# pcb-bldc-servo-3.net
KiCad netlist of a schematic drawn in EAGLE
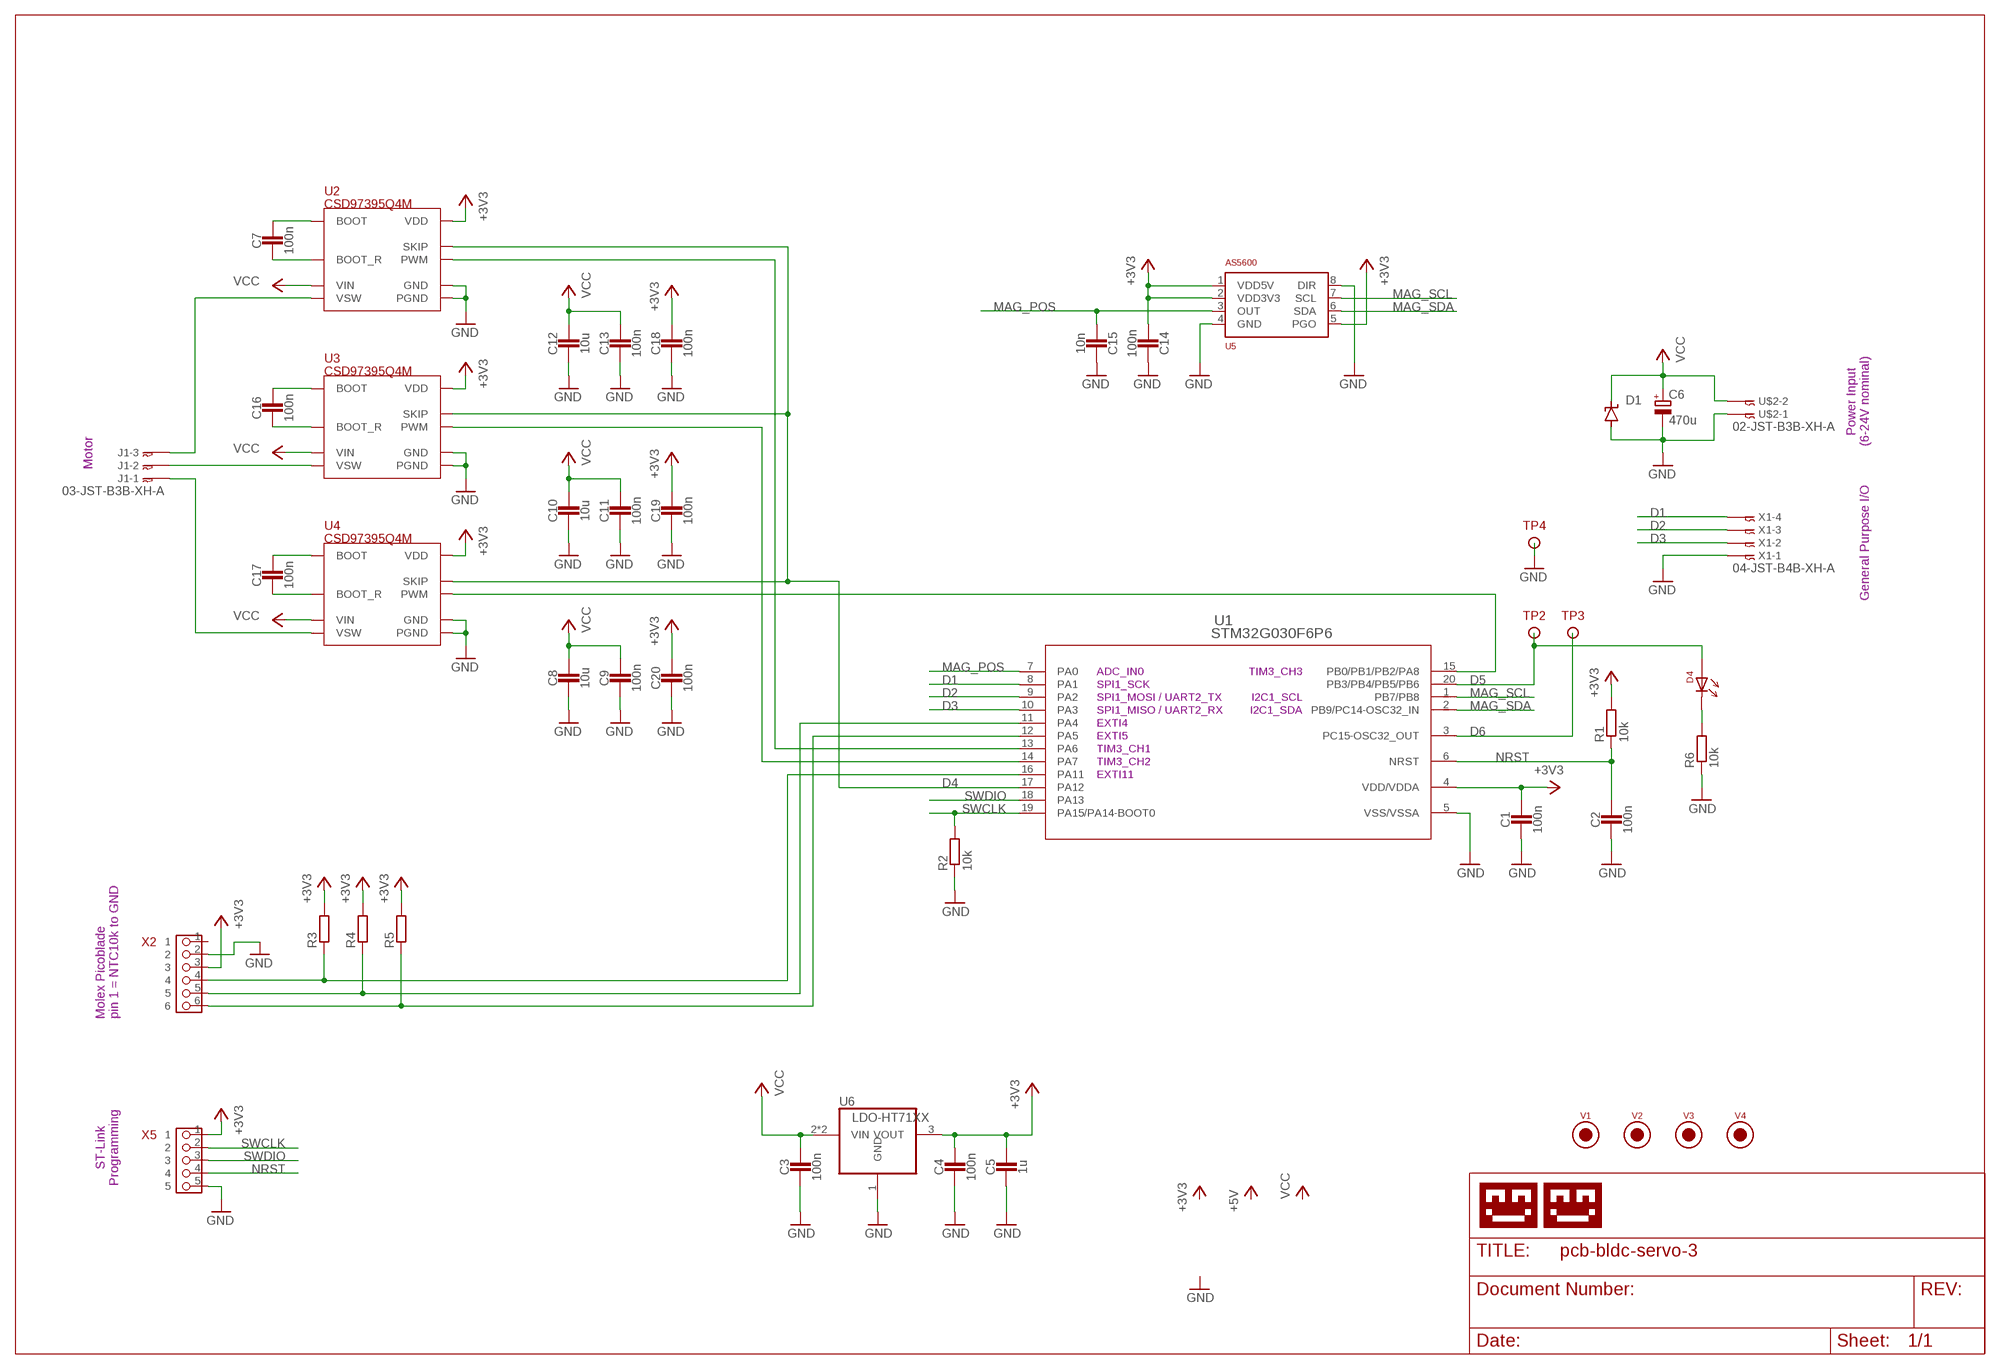
[diagram p0: schematic, sheet 1]

(export (version "E")
  (design (tool "Eeschema 10.0.6"))
  (components
    (comp (ref "C1")
      (value "100n")
      (footprint "eagle-import:0603_CAP")
      (libsource (lib "eagle-import") (part "CAPACITOR0603_CAP"))
    )
    (comp (ref "C2")
      (value "100n")
      (footprint "eagle-import:0603_CAP")
      (libsource (lib "eagle-import") (part "CAPACITOR0603_CAP"))
    )
    (comp (ref "C3")
      (value "100n")
      (footprint "eagle-import:0603_CAP")
      (libsource (lib "eagle-import") (part "CAPACITOR0603_CAP"))
    )
    (comp (ref "C4")
      (value "100n")
      (footprint "eagle-import:0603_CAP")
      (libsource (lib "eagle-import") (part "CAPACITOR0603_CAP"))
    )
    (comp (ref "C5")
      (value "1u")
      (footprint "eagle-import:0603_CAP")
      (libsource (lib "eagle-import") (part "CAPACITOR0603_CAP"))
    )
    (comp (ref "C6")
      (value "470u")
      (footprint "eagle-import:153CLV-1010")
      (libsource (lib "eagle-import") (part "CPOL-EU153CLV-1010"))
    )
    (comp (ref "C7")
      (value "100n")
      (footprint "eagle-import:0603_CAP")
      (libsource (lib "eagle-import") (part "CAPACITOR0603_CAP"))
    )
    (comp (ref "C8")
      (value "10u")
      (footprint "eagle-import:1206_CAP")
      (libsource (lib "eagle-import") (part "CAPACITOR1206_CAP"))
    )
    (comp (ref "C9")
      (value "100n")
      (footprint "eagle-import:0603_CAP")
      (libsource (lib "eagle-import") (part "CAPACITOR0603_CAP"))
    )
    (comp (ref "C10")
      (value "10u")
      (footprint "eagle-import:1206_CAP")
      (libsource (lib "eagle-import") (part "CAPACITOR1206_CAP"))
    )
    (comp (ref "C11")
      (value "100n")
      (footprint "eagle-import:0603_CAP")
      (libsource (lib "eagle-import") (part "CAPACITOR0603_CAP"))
    )
    (comp (ref "C12")
      (value "10u")
      (footprint "eagle-import:1206_CAP")
      (libsource (lib "eagle-import") (part "CAPACITOR1206_CAP"))
    )
    (comp (ref "C13")
      (value "100n")
      (footprint "eagle-import:0603_CAP")
      (libsource (lib "eagle-import") (part "CAPACITOR0603_CAP"))
    )
    (comp (ref "C14")
      (value "100n")
      (footprint "eagle-import:0603_CAP")
      (libsource (lib "eagle-import") (part "CAPACITOR0603_CAP"))
    )
    (comp (ref "C15")
      (value "10n")
      (footprint "eagle-import:0603_CAP")
      (libsource (lib "eagle-import") (part "CAPACITOR0603_CAP"))
    )
    (comp (ref "C16")
      (value "100n")
      (footprint "eagle-import:0603_CAP")
      (libsource (lib "eagle-import") (part "CAPACITOR0603_CAP"))
    )
    (comp (ref "C17")
      (value "100n")
      (footprint "eagle-import:0603_CAP")
      (libsource (lib "eagle-import") (part "CAPACITOR0603_CAP"))
    )
    (comp (ref "C18")
      (value "100n")
      (footprint "eagle-import:0603_CAP")
      (libsource (lib "eagle-import") (part "CAPACITOR0603_CAP"))
    )
    (comp (ref "C19")
      (value "100n")
      (footprint "eagle-import:0603_CAP")
      (libsource (lib "eagle-import") (part "CAPACITOR0603_CAP"))
    )
    (comp (ref "C20")
      (value "100n")
      (footprint "eagle-import:0603_CAP")
      (libsource (lib "eagle-import") (part "CAPACITOR0603_CAP"))
    )
    (comp (ref "D1")
      (value "SUPPRESSOR-SMBJ")
      (footprint "eagle-import:SMBJ")
      (libsource (lib "eagle-import") (part "SUPPRESSOR-SMBJ"))
    )
    (comp (ref "D4")
      (value "LED-0805")
      (footprint "eagle-import:0805-DOT")
      (libsource (lib "eagle-import") (part "LED-0805"))
    )
    (comp (ref "J1")
      (value "03-JST-B3B-XH-A")
      (footprint "eagle-import:B3B-XH")
      (libsource (lib "eagle-import") (part "03-JST-B3B-XH-A"))
    )
    (comp (ref "R1")
      (value "10k")
      (footprint "eagle-import:0603-RES")
      (libsource (lib "eagle-import") (part "RESISTOR0603_RES"))
    )
    (comp (ref "R2")
      (value "10k")
      (footprint "eagle-import:0603-RES")
      (libsource (lib "eagle-import") (part "RESISTOR0603_RES"))
    )
    (comp (ref "R3")
      (value "RESISTOR0603_RES")
      (footprint "eagle-import:0603-RES")
      (libsource (lib "eagle-import") (part "RESISTOR0603_RES"))
    )
    (comp (ref "R4")
      (value "RESISTOR0603_RES")
      (footprint "eagle-import:0603-RES")
      (libsource (lib "eagle-import") (part "RESISTOR0603_RES"))
    )
    (comp (ref "R5")
      (value "RESISTOR0603_RES")
      (footprint "eagle-import:0603-RES")
      (libsource (lib "eagle-import") (part "RESISTOR0603_RES"))
    )
    (comp (ref "R6")
      (value "10k")
      (footprint "eagle-import:0603-RES")
      (libsource (lib "eagle-import") (part "RESISTOR0603_RES"))
    )
    (comp (ref "TP2")
      (value "TESTPIN1MM")
      (footprint "eagle-import:PIN-SMD-1X1-TEST_1M0")
      (libsource (lib "eagle-import") (part "TESTPIN1MM"))
    )
    (comp (ref "TP3")
      (value "TESTPIN1MM")
      (footprint "eagle-import:PIN-SMD-1X1-TEST_1M0")
      (libsource (lib "eagle-import") (part "TESTPIN1MM"))
    )
    (comp (ref "TP4")
      (value "TESTPIN1MM")
      (footprint "eagle-import:PIN-SMD-1X1-TEST_1M0")
      (libsource (lib "eagle-import") (part "TESTPIN1MM"))
    )
    (comp (ref "U$1")
      (value "LOGO-TOBENG-1MM-FINISH")
      (footprint "eagle-import:TOBENG-1MM-FINISH")
      (libsource (lib "eagle-import") (part "LOGO-TOBENG-1MM-FINISH"))
    )
    (comp (ref "U$2")
      (value "02-JST-B3B-XH-A")
      (footprint "eagle-import:B2B-XH")
      (libsource (lib "eagle-import") (part "02-JST-B3B-XH-A"))
    )
    (comp (ref "U$3")
      (value "LOGO-TOBENG-4MM-FINISH")
      (footprint "eagle-import:TOBENG-4MM-FINISH")
      (libsource (lib "eagle-import") (part "LOGO-TOBENG-4MM-FINISH"))
    )
    (comp (ref "U1")
      (value "STM32G030F6P6")
      (footprint "eagle-import:TSSOP20")
      (fields (field (name "COPYRIGHT") "Copyright (C) 2024 Ultra Librarian. All rights reserved."))
      (libsource (lib "eagle-import") (part "STM32G030F6P6"))
    )
    (comp (ref "U2")
      (value "CSD97395Q4M")
      (footprint "eagle-import:CSD97395Q4M")
      (libsource (lib "eagle-import") (part "CSD97395Q4M"))
    )
    (comp (ref "U3")
      (value "CSD97395Q4M")
      (footprint "eagle-import:CSD97395Q4M")
      (libsource (lib "eagle-import") (part "CSD97395Q4M"))
    )
    (comp (ref "U4")
      (value "CSD97395Q4M")
      (footprint "eagle-import:CSD97395Q4M")
      (libsource (lib "eagle-import") (part "CSD97395Q4M"))
    )
    (comp (ref "U5")
      (value "AS5600")
      (footprint "eagle-import:SOIC-8")
      (libsource (lib "eagle-import") (part "AS5600"))
    )
    (comp (ref "U6")
      (value "LDO-HT71XX")
      (footprint "eagle-import:SOT-89")
      (libsource (lib "eagle-import") (part "LDO-HT71XX"))
    )
    (comp (ref "V1")
      (value "FIDUCIAL2MM")
      (footprint "eagle-import:FIDUCIAL_2MM")
      (libsource (lib "eagle-import") (part "FIDUCIAL2MM"))
    )
    (comp (ref "V2")
      (value "FIDUCIAL2MM")
      (footprint "eagle-import:FIDUCIAL_2MM")
      (libsource (lib "eagle-import") (part "FIDUCIAL2MM"))
    )
    (comp (ref "V3")
      (value "FIDUCIAL2MM")
      (footprint "eagle-import:FIDUCIAL_2MM")
      (libsource (lib "eagle-import") (part "FIDUCIAL2MM"))
    )
    (comp (ref "V4")
      (value "FIDUCIAL2MM")
      (footprint "eagle-import:FIDUCIAL_2MM")
      (libsource (lib "eagle-import") (part "FIDUCIAL2MM"))
    )
    (comp (ref "X1")
      (value "04-JST-B4B-XH-A")
      (footprint "eagle-import:B4B-XH")
      (libsource (lib "eagle-import") (part "04-JST-B4B-XH-A"))
    )
    (comp (ref "X2")
      (value "PIN_6X1")
      (footprint "eagle-import:PIN_6X1_MOLEX_PICOBLADE")
      (libsource (lib "eagle-import") (part "PIN_6X1"))
    )
    (comp (ref "X5")
      (value "PIN_5X1HD")
      (footprint "eagle-import:PIN_5X1_HD")
      (libsource (lib "eagle-import") (part "PIN_5X1HD"))
    )
  )
  (nets
    (net (code "1") (name "+3V3") (class "Default")
      (node (ref "C1") (pin "1") (pinfunction "1_1") (pintype "bidirectional"))
      (node (ref "C14") (pin "1") (pinfunction "1_1") (pintype "bidirectional"))
      (node (ref "C18") (pin "1") (pinfunction "1_1") (pintype "bidirectional"))
      (node (ref "C19") (pin "1") (pinfunction "1_1") (pintype "bidirectional"))
      (node (ref "C20") (pin "1") (pinfunction "1_1") (pintype "bidirectional"))
      (node (ref "C4") (pin "1") (pinfunction "1_1") (pintype "bidirectional"))
      (node (ref "C5") (pin "1") (pinfunction "1_1") (pintype "bidirectional"))
      (node (ref "R1") (pin "2") (pinfunction "2_2") (pintype "passive"))
      (node (ref "R3") (pin "2") (pinfunction "2_2") (pintype "passive"))
      (node (ref "R4") (pin "2") (pinfunction "2_2") (pintype "passive"))
      (node (ref "R5") (pin "2") (pinfunction "2_2") (pintype "passive"))
      (node (ref "U1") (pin "4") (pinfunction "VDD/VDDA_4") (pintype "power_in"))
      (node (ref "U2") (pin "VDD") (pinfunction "VDD_VDD") (pintype "bidirectional"))
      (node (ref "U2") (pin "VDD1") (pinfunction "VDD_VDD1") (pintype "bidirectional"))
      (node (ref "U3") (pin "VDD") (pinfunction "VDD_VDD") (pintype "bidirectional"))
      (node (ref "U3") (pin "VDD1") (pinfunction "VDD_VDD1") (pintype "bidirectional"))
      (node (ref "U4") (pin "VDD") (pinfunction "VDD_VDD") (pintype "bidirectional"))
      (node (ref "U4") (pin "VDD1") (pinfunction "VDD_VDD1") (pintype "bidirectional"))
      (node (ref "U5") (pin "1") (pinfunction "VDD5V_1") (pintype "bidirectional"))
      (node (ref "U5") (pin "2") (pinfunction "VDD3V3_2") (pintype "bidirectional"))
      (node (ref "U5") (pin "5") (pinfunction "PGO_5") (pintype "bidirectional"))
      (node (ref "U6") (pin "3") (pinfunction "VOUT_3") (pintype "output"))
      (node (ref "X2") (pin "3") (pinfunction "3_3") (pintype "bidirectional"))
      (node (ref "X5") (pin "1") (pinfunction "1_1") (pintype "bidirectional"))
    )
    (net (code "3") (name "/D1") (class "Default")
      (node (ref "U1") (pin "8") (pinfunction "PA1_8") (pintype "bidirectional"))
      (node (ref "X1") (pin "P$4") (pinfunction "1_P$4") (pintype "passive"))
    )
    (net (code "4") (name "/D2") (class "Default")
      (node (ref "U1") (pin "9") (pinfunction "PA2_9") (pintype "bidirectional"))
      (node (ref "X1") (pin "P$3") (pinfunction "1_P$3") (pintype "passive"))
    )
    (net (code "5") (name "/D3") (class "Default")
      (node (ref "U1") (pin "10") (pinfunction "PA3_10") (pintype "bidirectional"))
      (node (ref "X1") (pin "P$2") (pinfunction "1_P$2") (pintype "passive"))
    )
    (net (code "6") (name "/D4") (class "Default")
      (node (ref "U1") (pin "17") (pinfunction "PA12_17") (pintype "bidirectional"))
      (node (ref "U2") (pin "SKIP") (pinfunction "SKIP_SKIP") (pintype "bidirectional"))
      (node (ref "U2") (pin "SKIP1") (pinfunction "SKIP_SKIP1") (pintype "bidirectional"))
      (node (ref "U3") (pin "SKIP") (pinfunction "SKIP_SKIP") (pintype "bidirectional"))
      (node (ref "U3") (pin "SKIP1") (pinfunction "SKIP_SKIP1") (pintype "bidirectional"))
      (node (ref "U4") (pin "SKIP") (pinfunction "SKIP_SKIP") (pintype "bidirectional"))
      (node (ref "U4") (pin "SKIP1") (pinfunction "SKIP_SKIP1") (pintype "bidirectional"))
    )
    (net (code "7") (name "/D5") (class "Default")
      (node (ref "D4") (pin "1") (pinfunction "1_1") (pintype "bidirectional"))
      (node (ref "TP2") (pin "1") (pinfunction "1_1") (pintype "bidirectional"))
      (node (ref "U1") (pin "20") (pinfunction "PB3/PB4/PB5/PB6_20") (pintype "bidirectional"))
    )
    (net (code "8") (name "/D6") (class "Default")
      (node (ref "TP3") (pin "1") (pinfunction "1_1") (pintype "bidirectional"))
      (node (ref "U1") (pin "3") (pinfunction "PC15-OSC32_OUT_3") (pintype "bidirectional"))
    )
    (net (code "9") (name "/MAG_POS") (class "Default")
      (node (ref "C15") (pin "1") (pinfunction "1_1") (pintype "bidirectional"))
      (node (ref "U1") (pin "7") (pinfunction "PA0_7") (pintype "bidirectional"))
      (node (ref "U5") (pin "3") (pinfunction "OUT_3") (pintype "bidirectional"))
    )
    (net (code "10") (name "/MAG_SCL") (class "Default")
      (node (ref "U1") (pin "1") (pinfunction "PB7/PB8_1") (pintype "bidirectional"))
      (node (ref "U5") (pin "7") (pinfunction "SCL_7") (pintype "bidirectional"))
    )
    (net (code "11") (name "/MAG_SDA") (class "Default")
      (node (ref "U1") (pin "2") (pinfunction "PB9/PC14-OSC32_IN_2") (pintype "bidirectional"))
      (node (ref "U5") (pin "6") (pinfunction "SDA_6") (pintype "bidirectional"))
    )
    (net (code "12") (name "/NRST") (class "Default")
      (node (ref "C2") (pin "1") (pinfunction "1_1") (pintype "bidirectional"))
      (node (ref "R1") (pin "1") (pinfunction "1_1") (pintype "passive"))
      (node (ref "U1") (pin "6") (pinfunction "NRST_6") (pintype "bidirectional"))
      (node (ref "X5") (pin "4") (pinfunction "4_4") (pintype "bidirectional"))
    )
    (net (code "13") (name "/SWCLK") (class "Default")
      (node (ref "R2") (pin "2") (pinfunction "2_2") (pintype "passive"))
      (node (ref "U1") (pin "19") (pinfunction "PA15/PA14-BOOT0_19") (pintype "bidirectional"))
      (node (ref "X5") (pin "2") (pinfunction "2_2") (pintype "bidirectional"))
    )
    (net (code "14") (name "/SWDIO") (class "Default")
      (node (ref "U1") (pin "18") (pinfunction "PA13_18") (pintype "bidirectional"))
      (node (ref "X5") (pin "3") (pinfunction "3_3") (pintype "bidirectional"))
    )
    (net (code "15") (name "GND") (class "Default")
      (node (ref "C1") (pin "2") (pinfunction "2_2") (pintype "bidirectional"))
      (node (ref "C10") (pin "2") (pinfunction "2_2") (pintype "bidirectional"))
      (node (ref "C11") (pin "2") (pinfunction "2_2") (pintype "bidirectional"))
      (node (ref "C12") (pin "2") (pinfunction "2_2") (pintype "bidirectional"))
      (node (ref "C13") (pin "2") (pinfunction "2_2") (pintype "bidirectional"))
      (node (ref "C14") (pin "2") (pinfunction "2_2") (pintype "bidirectional"))
      (node (ref "C15") (pin "2") (pinfunction "2_2") (pintype "bidirectional"))
      (node (ref "C18") (pin "2") (pinfunction "2_2") (pintype "bidirectional"))
      (node (ref "C19") (pin "2") (pinfunction "2_2") (pintype "bidirectional"))
      (node (ref "C2") (pin "2") (pinfunction "2_2") (pintype "bidirectional"))
      (node (ref "C20") (pin "2") (pinfunction "2_2") (pintype "bidirectional"))
      (node (ref "C3") (pin "2") (pinfunction "2_2") (pintype "bidirectional"))
      (node (ref "C4") (pin "2") (pinfunction "2_2") (pintype "bidirectional"))
      (node (ref "C5") (pin "2") (pinfunction "2_2") (pintype "bidirectional"))
      (node (ref "C6") (pin "-") (pinfunction "-_-") (pintype "passive"))
      (node (ref "C8") (pin "2") (pinfunction "2_2") (pintype "bidirectional"))
      (node (ref "C9") (pin "2") (pinfunction "2_2") (pintype "bidirectional"))
      (node (ref "D1") (pin "A") (pinfunction "A_A") (pintype "passive"))
      (node (ref "R2") (pin "1") (pinfunction "1_1") (pintype "passive"))
      (node (ref "R6") (pin "1") (pinfunction "1_1") (pintype "passive"))
      (node (ref "TP4") (pin "1") (pinfunction "1_1") (pintype "bidirectional"))
      (node (ref "U$2") (pin "P$1") (pinfunction "1_P$1") (pintype "passive"))
      (node (ref "U1") (pin "5") (pinfunction "VSS/VSSA_5") (pintype "power_in"))
      (node (ref "U2") (pin "GND") (pinfunction "GND_GND") (pintype "bidirectional"))
      (node (ref "U2") (pin "GND1") (pinfunction "GND_GND1") (pintype "bidirectional"))
      (node (ref "U2") (pin "PGND") (pinfunction "PGND_PGND") (pintype "bidirectional"))
      (node (ref "U3") (pin "GND") (pinfunction "GND_GND") (pintype "bidirectional"))
      (node (ref "U3") (pin "GND1") (pinfunction "GND_GND1") (pintype "bidirectional"))
      (node (ref "U3") (pin "PGND") (pinfunction "PGND_PGND") (pintype "bidirectional"))
      (node (ref "U4") (pin "GND") (pinfunction "GND_GND") (pintype "bidirectional"))
      (node (ref "U4") (pin "GND1") (pinfunction "GND_GND1") (pintype "bidirectional"))
      (node (ref "U4") (pin "PGND") (pinfunction "PGND_PGND") (pintype "bidirectional"))
      (node (ref "U5") (pin "4") (pinfunction "GND_4") (pintype "bidirectional"))
      (node (ref "U5") (pin "8") (pinfunction "DIR_8") (pintype "bidirectional"))
      (node (ref "U6") (pin "1") (pinfunction "GND_1") (pintype "power_in"))
      (node (ref "X1") (pin "P$1") (pinfunction "1_P$1") (pintype "passive"))
      (node (ref "X2") (pin "2") (pinfunction "2_2") (pintype "bidirectional"))
      (node (ref "X5") (pin "5") (pinfunction "5_5") (pintype "bidirectional"))
    )
    (net (code "16") (name "Net-(C7-Pad1)") (class "Default")
      (node (ref "C7") (pin "1") (pinfunction "1_1") (pintype "bidirectional"))
      (node (ref "U2") (pin "BOOT") (pinfunction "BOOT_BOOT") (pintype "bidirectional"))
      (node (ref "U2") (pin "BOOT1") (pinfunction "BOOT_BOOT1") (pintype "bidirectional"))
    )
    (net (code "17") (name "Net-(C7-Pad2)") (class "Default")
      (node (ref "C7") (pin "2") (pinfunction "2_2") (pintype "bidirectional"))
      (node (ref "U2") (pin "BOOT_R") (pinfunction "BOOT_R_BOOT_R") (pintype "bidirectional"))
      (node (ref "U2") (pin "BOOT_R1") (pinfunction "BOOT_R_BOOT_R1") (pintype "bidirectional"))
    )
    (net (code "18") (name "Net-(C16-Pad1)") (class "Default")
      (node (ref "C16") (pin "1") (pinfunction "1_1") (pintype "bidirectional"))
      (node (ref "U3") (pin "BOOT") (pinfunction "BOOT_BOOT") (pintype "bidirectional"))
      (node (ref "U3") (pin "BOOT1") (pinfunction "BOOT_BOOT1") (pintype "bidirectional"))
    )
    (net (code "19") (name "Net-(C16-Pad2)") (class "Default")
      (node (ref "C16") (pin "2") (pinfunction "2_2") (pintype "bidirectional"))
      (node (ref "U3") (pin "BOOT_R") (pinfunction "BOOT_R_BOOT_R") (pintype "bidirectional"))
      (node (ref "U3") (pin "BOOT_R1") (pinfunction "BOOT_R_BOOT_R1") (pintype "bidirectional"))
    )
    (net (code "20") (name "Net-(C17-Pad1)") (class "Default")
      (node (ref "C17") (pin "1") (pinfunction "1_1") (pintype "bidirectional"))
      (node (ref "U4") (pin "BOOT") (pinfunction "BOOT_BOOT") (pintype "bidirectional"))
      (node (ref "U4") (pin "BOOT1") (pinfunction "BOOT_BOOT1") (pintype "bidirectional"))
    )
    (net (code "21") (name "Net-(C17-Pad2)") (class "Default")
      (node (ref "C17") (pin "2") (pinfunction "2_2") (pintype "bidirectional"))
      (node (ref "U4") (pin "BOOT_R") (pinfunction "BOOT_R_BOOT_R") (pintype "bidirectional"))
      (node (ref "U4") (pin "BOOT_R1") (pinfunction "BOOT_R_BOOT_R1") (pintype "bidirectional"))
    )
    (net (code "22") (name "Net-(D4-Pad2)") (class "Default")
      (node (ref "D4") (pin "2") (pinfunction "2_2") (pintype "bidirectional"))
      (node (ref "R6") (pin "2") (pinfunction "2_2") (pintype "passive"))
    )
    (net (code "23") (name "Net-(J1A-1)") (class "Default")
      (node (ref "J1") (pin "P$1") (pinfunction "1_P$1") (pintype "passive"))
      (node (ref "U4") (pin "VSW") (pinfunction "VSW_VSW") (pintype "bidirectional"))
      (node (ref "U4") (pin "VSW1") (pinfunction "VSW_VSW1") (pintype "bidirectional"))
      (node (ref "U4") (pin "VSW2") (pinfunction "VSW_VSW2") (pintype "bidirectional"))
      (node (ref "U4") (pin "VSW3") (pinfunction "VSW_VSW3") (pintype "bidirectional"))
      (node (ref "U4") (pin "VSW4") (pinfunction "VSW_VSW4") (pintype "bidirectional"))
      (node (ref "U4") (pin "VSW5") (pinfunction "VSW_VSW5") (pintype "bidirectional"))
      (node (ref "U4") (pin "VSW6") (pinfunction "VSW_VSW6") (pintype "bidirectional"))
    )
    (net (code "24") (name "Net-(J1B-1)") (class "Default")
      (node (ref "J1") (pin "P$2") (pinfunction "1_P$2") (pintype "passive"))
      (node (ref "U3") (pin "VSW") (pinfunction "VSW_VSW") (pintype "bidirectional"))
      (node (ref "U3") (pin "VSW1") (pinfunction "VSW_VSW1") (pintype "bidirectional"))
      (node (ref "U3") (pin "VSW2") (pinfunction "VSW_VSW2") (pintype "bidirectional"))
      (node (ref "U3") (pin "VSW3") (pinfunction "VSW_VSW3") (pintype "bidirectional"))
      (node (ref "U3") (pin "VSW4") (pinfunction "VSW_VSW4") (pintype "bidirectional"))
      (node (ref "U3") (pin "VSW5") (pinfunction "VSW_VSW5") (pintype "bidirectional"))
      (node (ref "U3") (pin "VSW6") (pinfunction "VSW_VSW6") (pintype "bidirectional"))
    )
    (net (code "25") (name "Net-(J1C-1)") (class "Default")
      (node (ref "J1") (pin "P$3") (pinfunction "1_P$3") (pintype "passive"))
      (node (ref "U2") (pin "VSW") (pinfunction "VSW_VSW") (pintype "bidirectional"))
      (node (ref "U2") (pin "VSW1") (pinfunction "VSW_VSW1") (pintype "bidirectional"))
      (node (ref "U2") (pin "VSW2") (pinfunction "VSW_VSW2") (pintype "bidirectional"))
      (node (ref "U2") (pin "VSW3") (pinfunction "VSW_VSW3") (pintype "bidirectional"))
      (node (ref "U2") (pin "VSW4") (pinfunction "VSW_VSW4") (pintype "bidirectional"))
      (node (ref "U2") (pin "VSW5") (pinfunction "VSW_VSW5") (pintype "bidirectional"))
      (node (ref "U2") (pin "VSW6") (pinfunction "VSW_VSW6") (pintype "bidirectional"))
    )
    (net (code "26") (name "Net-(U1-PA4)") (class "Default")
      (node (ref "R4") (pin "1") (pinfunction "1_1") (pintype "passive"))
      (node (ref "U1") (pin "11") (pinfunction "PA4_11") (pintype "bidirectional"))
      (node (ref "X2") (pin "5") (pinfunction "5_5") (pintype "bidirectional"))
    )
    (net (code "27") (name "Net-(U1-PA5)") (class "Default")
      (node (ref "R5") (pin "1") (pinfunction "1_1") (pintype "passive"))
      (node (ref "U1") (pin "12") (pinfunction "PA5_12") (pintype "bidirectional"))
      (node (ref "X2") (pin "6") (pinfunction "6_6") (pintype "bidirectional"))
    )
    (net (code "28") (name "Net-(U1-PA6)") (class "Default")
      (node (ref "U1") (pin "13") (pinfunction "PA6_13") (pintype "bidirectional"))
      (node (ref "U2") (pin "PWM") (pinfunction "PWM_PWM") (pintype "bidirectional"))
      (node (ref "U2") (pin "PWM1") (pinfunction "PWM_PWM1") (pintype "bidirectional"))
    )
    (net (code "29") (name "Net-(U1-PA7)") (class "Default")
      (node (ref "U1") (pin "14") (pinfunction "PA7_14") (pintype "bidirectional"))
      (node (ref "U3") (pin "PWM") (pinfunction "PWM_PWM") (pintype "bidirectional"))
      (node (ref "U3") (pin "PWM1") (pinfunction "PWM_PWM1") (pintype "bidirectional"))
    )
    (net (code "30") (name "Net-(U1-PA11)") (class "Default")
      (node (ref "R3") (pin "1") (pinfunction "1_1") (pintype "passive"))
      (node (ref "U1") (pin "16") (pinfunction "PA11_16") (pintype "bidirectional"))
      (node (ref "X2") (pin "4") (pinfunction "4_4") (pintype "bidirectional"))
    )
    (net (code "31") (name "Net-(U1-PB0{slash}PB1{slash}PB2{slash}PA8)") (class "Default")
      (node (ref "U1") (pin "15") (pinfunction "PB0/PB1/PB2/PA8_15") (pintype "bidirectional"))
      (node (ref "U4") (pin "PWM") (pinfunction "PWM_PWM") (pintype "bidirectional"))
      (node (ref "U4") (pin "PWM1") (pinfunction "PWM_PWM1") (pintype "bidirectional"))
    )
    (net (code "32") (name "VCC") (class "Default")
      (node (ref "C10") (pin "1") (pinfunction "1_1") (pintype "bidirectional"))
      (node (ref "C11") (pin "1") (pinfunction "1_1") (pintype "bidirectional"))
      (node (ref "C12") (pin "1") (pinfunction "1_1") (pintype "bidirectional"))
      (node (ref "C13") (pin "1") (pinfunction "1_1") (pintype "bidirectional"))
      (node (ref "C3") (pin "1") (pinfunction "1_1") (pintype "bidirectional"))
      (node (ref "C6") (pin "+") (pinfunction "+_+") (pintype "passive"))
      (node (ref "C8") (pin "1") (pinfunction "1_1") (pintype "bidirectional"))
      (node (ref "C9") (pin "1") (pinfunction "1_1") (pintype "bidirectional"))
      (node (ref "D1") (pin "C") (pinfunction "C_C") (pintype "passive"))
      (node (ref "U$2") (pin "P$2") (pinfunction "1_P$2") (pintype "passive"))
      (node (ref "U2") (pin "VIN") (pinfunction "VIN_VIN") (pintype "bidirectional"))
      (node (ref "U2") (pin "VIN1") (pinfunction "VIN_VIN1") (pintype "bidirectional"))
      (node (ref "U2") (pin "VIN2") (pinfunction "VIN_VIN2") (pintype "bidirectional"))
      (node (ref "U2") (pin "VIN3") (pinfunction "VIN_VIN3") (pintype "bidirectional"))
      (node (ref "U2") (pin "VIN4") (pinfunction "VIN_VIN4") (pintype "bidirectional"))
      (node (ref "U2") (pin "VIN5") (pinfunction "VIN_VIN5") (pintype "bidirectional"))
      (node (ref "U2") (pin "VIN6") (pinfunction "VIN_VIN6") (pintype "bidirectional"))
      (node (ref "U3") (pin "VIN") (pinfunction "VIN_VIN") (pintype "bidirectional"))
      (node (ref "U3") (pin "VIN1") (pinfunction "VIN_VIN1") (pintype "bidirectional"))
      (node (ref "U3") (pin "VIN2") (pinfunction "VIN_VIN2") (pintype "bidirectional"))
      (node (ref "U3") (pin "VIN3") (pinfunction "VIN_VIN3") (pintype "bidirectional"))
      (node (ref "U3") (pin "VIN4") (pinfunction "VIN_VIN4") (pintype "bidirectional"))
      (node (ref "U3") (pin "VIN5") (pinfunction "VIN_VIN5") (pintype "bidirectional"))
      (node (ref "U3") (pin "VIN6") (pinfunction "VIN_VIN6") (pintype "bidirectional"))
      (node (ref "U4") (pin "VIN") (pinfunction "VIN_VIN") (pintype "bidirectional"))
      (node (ref "U4") (pin "VIN1") (pinfunction "VIN_VIN1") (pintype "bidirectional"))
      (node (ref "U4") (pin "VIN2") (pinfunction "VIN_VIN2") (pintype "bidirectional"))
      (node (ref "U4") (pin "VIN3") (pinfunction "VIN_VIN3") (pintype "bidirectional"))
      (node (ref "U4") (pin "VIN4") (pinfunction "VIN_VIN4") (pintype "bidirectional"))
      (node (ref "U4") (pin "VIN5") (pinfunction "VIN_VIN5") (pintype "bidirectional"))
      (node (ref "U4") (pin "VIN6") (pinfunction "VIN_VIN6") (pintype "bidirectional"))
      (node (ref "U6") (pin "2") (pinfunction "VIN_2") (pintype "input"))
      (node (ref "U6") (pin "2@1") (pinfunction "VIN_2@1") (pintype "input"))
    )
    (net (code "33") (name "unconnected-(X2-Pad1)") (class "Default")
      (node (ref "X2") (pin "1") (pinfunction "1_1") (pintype "bidirectional"))
    )
  )
)
